# M7050D.net
KiCad netlist of a schematic drawn in EAGLE
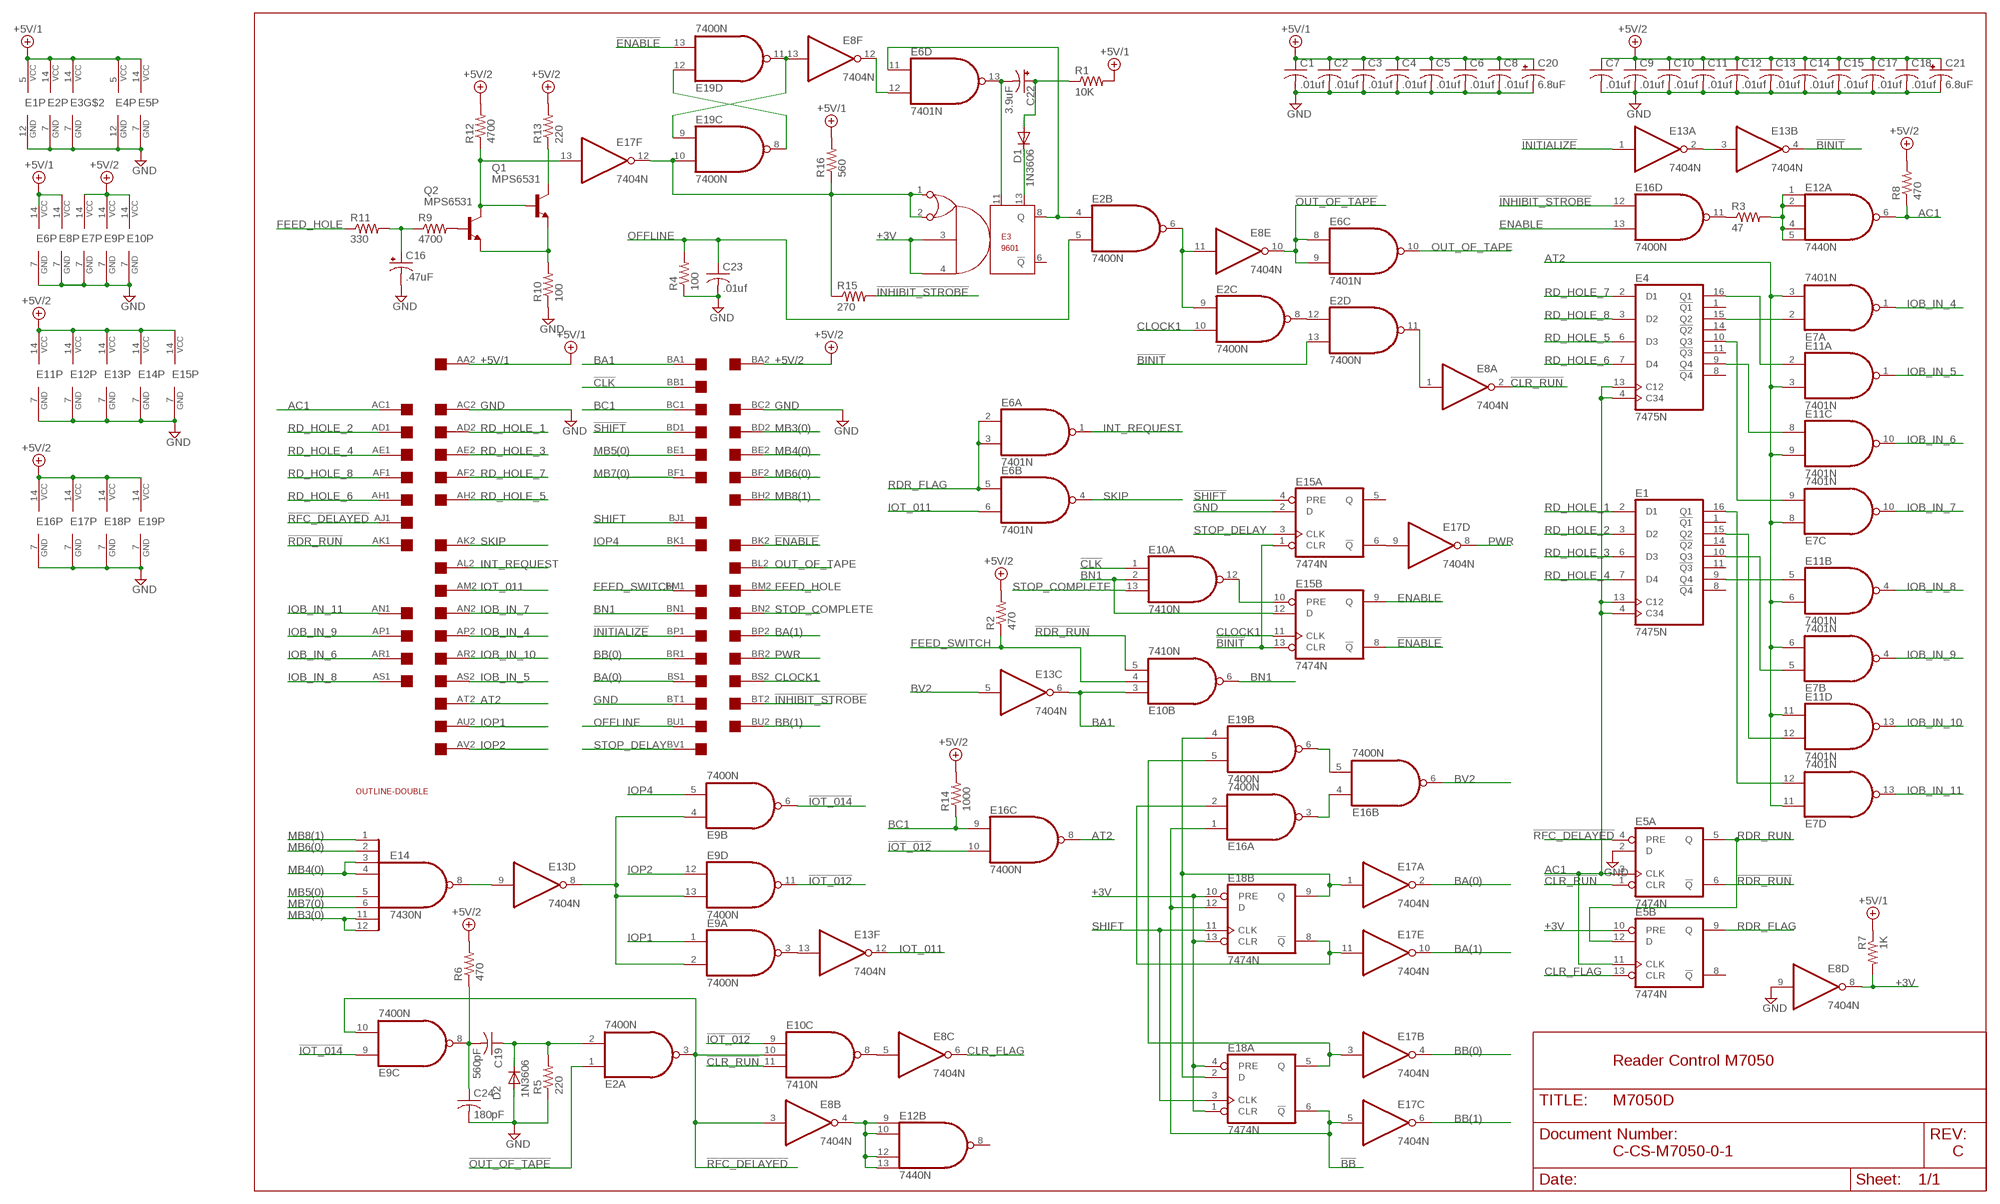
[diagram p0: schematic, sheet 1]

(export (version "E")
  (design (tool "Eeschema 10.0.6"))
  (components
    (comp (ref "C1")
      (value ".01uf")
      (footprint "eagle-import:C075-032X103")
      (libsource (lib "eagle-import") (part "C-US075-032X103"))
    )
    (comp (ref "C2")
      (value ".01uf")
      (footprint "eagle-import:C075-032X103")
      (libsource (lib "eagle-import") (part "C-US075-032X103"))
    )
    (comp (ref "C3")
      (value ".01uf")
      (footprint "eagle-import:C075-032X103")
      (libsource (lib "eagle-import") (part "C-US075-032X103"))
    )
    (comp (ref "C4")
      (value ".01uf")
      (footprint "eagle-import:C075-032X103")
      (libsource (lib "eagle-import") (part "C-US075-032X103"))
    )
    (comp (ref "C5")
      (value ".01uf")
      (footprint "eagle-import:C075-032X103")
      (libsource (lib "eagle-import") (part "C-US075-032X103"))
    )
    (comp (ref "C6")
      (value ".01uf")
      (footprint "eagle-import:C075-032X103")
      (libsource (lib "eagle-import") (part "C-US075-032X103"))
    )
    (comp (ref "C7")
      (value ".01uf")
      (footprint "eagle-import:C075-032X103")
      (libsource (lib "eagle-import") (part "C-US075-032X103"))
    )
    (comp (ref "C8")
      (value ".01uf")
      (footprint "eagle-import:C075-032X103")
      (libsource (lib "eagle-import") (part "C-US075-032X103"))
    )
    (comp (ref "C9")
      (value ".01uf")
      (footprint "eagle-import:C075-032X103")
      (libsource (lib "eagle-import") (part "C-US075-032X103"))
    )
    (comp (ref "C10")
      (value ".01uf")
      (footprint "eagle-import:C075-032X103")
      (libsource (lib "eagle-import") (part "C-US075-032X103"))
    )
    (comp (ref "C11")
      (value ".01uf")
      (footprint "eagle-import:C075-032X103")
      (libsource (lib "eagle-import") (part "C-US075-032X103"))
    )
    (comp (ref "C12")
      (value ".01uf")
      (footprint "eagle-import:C075-032X103")
      (libsource (lib "eagle-import") (part "C-US075-032X103"))
    )
    (comp (ref "C13")
      (value ".01uf")
      (footprint "eagle-import:C075-032X103")
      (libsource (lib "eagle-import") (part "C-US075-032X103"))
    )
    (comp (ref "C14")
      (value ".01uf")
      (footprint "eagle-import:C075-032X103")
      (libsource (lib "eagle-import") (part "C-US075-032X103"))
    )
    (comp (ref "C15")
      (value ".01uf")
      (footprint "eagle-import:C075-032X103")
      (libsource (lib "eagle-import") (part "C-US075-032X103"))
    )
    (comp (ref "C16")
      (value ".47uF")
      (footprint "eagle-import:E15-5")
      (libsource (lib "eagle-import") (part "CPOL-USE15-5AXIAL"))
    )
    (comp (ref "C17")
      (value ".01uf")
      (footprint "eagle-import:C075-032X103")
      (libsource (lib "eagle-import") (part "C-US075-032X103"))
    )
    (comp (ref "C18")
      (value ".01uf")
      (footprint "eagle-import:C075-032X103")
      (libsource (lib "eagle-import") (part "C-US075-032X103"))
    )
    (comp (ref "C19")
      (value "560pF")
      (footprint "eagle-import:C075-032X103")
      (libsource (lib "eagle-import") (part "C-US075-032X103"))
    )
    (comp (ref "C20")
      (value "6.8uF")
      (footprint "eagle-import:E12-8")
      (libsource (lib "eagle-import") (part "CPOL-USE20-8AXIAL"))
    )
    (comp (ref "C21")
      (value "6.8uF")
      (footprint "eagle-import:E12-8")
      (libsource (lib "eagle-import") (part "CPOL-USE20-8AXIAL"))
    )
    (comp (ref "C22")
      (value "3.9uF")
      (footprint "eagle-import:E15-5")
      (libsource (lib "eagle-import") (part "CPOL-USE15-5AXIAL"))
    )
    (comp (ref "C23")
      (value ".01uf")
      (footprint "eagle-import:C075-032X103")
      (libsource (lib "eagle-import") (part "C-US075-032X103"))
    )
    (comp (ref "C24")
      (value "180pF")
      (footprint "eagle-import:C075-032X103")
      (libsource (lib "eagle-import") (part "C-US075-032X103"))
    )
    (comp (ref "D1")
      (value "1N3606")
      (footprint "eagle-import:DO35-10")
      (libsource (lib "eagle-import") (part "1N4148DO35-10"))
    )
    (comp (ref "D2")
      (value "1N3606")
      (footprint "eagle-import:DO35-10")
      (libsource (lib "eagle-import") (part "1N4148DO35-10"))
    )
    (comp (ref "E1")
      (value "7475N")
      (footprint "eagle-import:DIL16")
      (libsource (lib "eagle-import") (part "7475N"))
    )
    (comp (ref "E2")
      (value "7400N")
      (footprint "eagle-import:DIL14")
      (libsource (lib "eagle-import") (part "7400N"))
    )
    (comp (ref "E3")
      (value "9601")
      (footprint "eagle-import:DIL14")
      (libsource (lib "eagle-import") (part "9601"))
    )
    (comp (ref "E4")
      (value "7475N")
      (footprint "eagle-import:DIL16")
      (libsource (lib "eagle-import") (part "7475N"))
    )
    (comp (ref "E5")
      (value "7474N")
      (footprint "eagle-import:DIL14")
      (libsource (lib "eagle-import") (part "7474NS"))
    )
    (comp (ref "E6")
      (value "7401N")
      (footprint "eagle-import:DIL14")
      (libsource (lib "eagle-import") (part "7401NLS"))
    )
    (comp (ref "E7")
      (value "7401N")
      (footprint "eagle-import:DIL14")
      (libsource (lib "eagle-import") (part "7401NLS"))
    )
    (comp (ref "E8")
      (value "7404N")
      (footprint "eagle-import:DIL14")
      (libsource (lib "eagle-import") (part "7404N"))
    )
    (comp (ref "E9")
      (value "7400N")
      (footprint "eagle-import:DIL14")
      (libsource (lib "eagle-import") (part "7400N"))
    )
    (comp (ref "E10")
      (value "7410N")
      (footprint "eagle-import:DIL14")
      (libsource (lib "eagle-import") (part "7410N"))
    )
    (comp (ref "E11")
      (value "7401N")
      (footprint "eagle-import:DIL14")
      (libsource (lib "eagle-import") (part "7401NLS"))
    )
    (comp (ref "E12")
      (value "7440N")
      (footprint "eagle-import:DIL14")
      (libsource (lib "eagle-import") (part "7420NS"))
    )
    (comp (ref "E13")
      (value "7404N")
      (footprint "eagle-import:DIL14")
      (libsource (lib "eagle-import") (part "7404N"))
    )
    (comp (ref "E14")
      (value "7430N")
      (footprint "eagle-import:DIL14")
      (libsource (lib "eagle-import") (part "7430N"))
    )
    (comp (ref "E15")
      (value "7474N")
      (footprint "eagle-import:DIL14")
      (libsource (lib "eagle-import") (part "7474NS"))
    )
    (comp (ref "E16")
      (value "7400N")
      (footprint "eagle-import:DIL14")
      (libsource (lib "eagle-import") (part "7400N"))
    )
    (comp (ref "E17")
      (value "7404N")
      (footprint "eagle-import:DIL14")
      (libsource (lib "eagle-import") (part "7404N"))
    )
    (comp (ref "E18")
      (value "7474N")
      (footprint "eagle-import:DIL14")
      (libsource (lib "eagle-import") (part "7474NS"))
    )
    (comp (ref "E19")
      (value "7400N")
      (footprint "eagle-import:DIL14")
      (libsource (lib "eagle-import") (part "7400N"))
    )
    (comp (ref "Q1")
      (value "MPS6531")
      (footprint "eagle-import:TO5")
      (libsource (lib "eagle-import") (part "2N2102"))
    )
    (comp (ref "Q2")
      (value "MPS6531")
      (footprint "eagle-import:TO5")
      (libsource (lib "eagle-import") (part "2N2102"))
    )
    (comp (ref "R1")
      (value "10K")
      (footprint "eagle-import:0207_10")
      (libsource (lib "eagle-import") (part "R-US_0207/10"))
    )
    (comp (ref "R2")
      (value "470")
      (footprint "eagle-import:0207_10")
      (libsource (lib "eagle-import") (part "R-US_0207/10"))
    )
    (comp (ref "R3")
      (value "47")
      (footprint "eagle-import:0207_10")
      (libsource (lib "eagle-import") (part "R-US_0207/10"))
    )
    (comp (ref "R4")
      (value "100")
      (footprint "eagle-import:0207_10")
      (libsource (lib "eagle-import") (part "R-US_0207/10"))
    )
    (comp (ref "R5")
      (value "220")
      (footprint "eagle-import:0207_10")
      (libsource (lib "eagle-import") (part "R-US_0207/10"))
    )
    (comp (ref "R6")
      (value "470")
      (footprint "eagle-import:0207_10")
      (libsource (lib "eagle-import") (part "R-US_0207/10"))
    )
    (comp (ref "R7")
      (value "1K")
      (footprint "eagle-import:0207_10")
      (libsource (lib "eagle-import") (part "R-US_0207/10"))
    )
    (comp (ref "R8")
      (value "470")
      (footprint "eagle-import:0207_10")
      (libsource (lib "eagle-import") (part "R-US_0207/10"))
    )
    (comp (ref "R9")
      (value "4700")
      (footprint "eagle-import:0207_10")
      (libsource (lib "eagle-import") (part "R-US_0207/10"))
    )
    (comp (ref "R10")
      (value "100")
      (footprint "eagle-import:0207_10")
      (libsource (lib "eagle-import") (part "R-US_0207/10"))
    )
    (comp (ref "R11")
      (value "330")
      (footprint "eagle-import:0207_10")
      (libsource (lib "eagle-import") (part "R-US_0207/10"))
    )
    (comp (ref "R12")
      (value "4700")
      (footprint "eagle-import:0207_10")
      (libsource (lib "eagle-import") (part "R-US_0207/10"))
    )
    (comp (ref "R13")
      (value "220")
      (footprint "eagle-import:0207_10")
      (libsource (lib "eagle-import") (part "R-US_0207/10"))
    )
    (comp (ref "R14")
      (value "1000")
      (footprint "eagle-import:0207_10")
      (libsource (lib "eagle-import") (part "R-US_0207/10"))
    )
    (comp (ref "R15")
      (value "270")
      (footprint "eagle-import:0207_10")
      (libsource (lib "eagle-import") (part "R-US_0207/10"))
    )
    (comp (ref "R16")
      (value "560")
      (footprint "eagle-import:0207_10")
      (libsource (lib "eagle-import") (part "R-US_0207/10"))
    )
    (comp (ref "U$5")
      (value "DOUBLE")
      (footprint "eagle-import:EDGE-CON4")
      (libsource (lib "eagle-import") (part "DOUBLE"))
    )
    (comp (ref "U$6")
      (value "OUTLINE-DOUBLE")
      (footprint "eagle-import:DOUBLE")
      (libsource (lib "eagle-import") (part "OUTLINE-DOUBLE"))
    )
  )
  (nets
    (net (code "1") (name "+5V{slash}1") (class "Default")
      (node (ref "C1") (pin "1") (pinfunction "1_1") (pintype "passive"))
      (node (ref "C2") (pin "1") (pinfunction "1_1") (pintype "passive"))
      (node (ref "C20") (pin "+") (pinfunction "+_+") (pintype "passive"))
      (node (ref "C3") (pin "1") (pinfunction "1_1") (pintype "passive"))
      (node (ref "C4") (pin "1") (pinfunction "1_1") (pintype "passive"))
      (node (ref "C5") (pin "1") (pinfunction "1_1") (pintype "passive"))
      (node (ref "C6") (pin "1") (pinfunction "1_1") (pintype "passive"))
      (node (ref "C8") (pin "1") (pinfunction "1_1") (pintype "passive"))
      (node (ref "E1") (pin "5") (pinfunction "VCC_5") (pintype "power_in"))
      (node (ref "E2") (pin "14") (pinfunction "VCC_14") (pintype "power_in"))
      (node (ref "E3") (pin "14") (pinfunction "VCC_14") (pintype "power_in"))
      (node (ref "E4") (pin "5") (pinfunction "VCC_5") (pintype "power_in"))
      (node (ref "E5") (pin "14") (pinfunction "VCC_14") (pintype "power_in"))
      (node (ref "E6") (pin "14") (pinfunction "VCC_14") (pintype "power_in"))
      (node (ref "E8") (pin "14") (pinfunction "VCC_14") (pintype "power_in"))
      (node (ref "R1") (pin "2") (pinfunction "2_2") (pintype "passive"))
      (node (ref "R16") (pin "2") (pinfunction "2_2") (pintype "passive"))
      (node (ref "R7") (pin "1") (pinfunction "1_1") (pintype "passive"))
      (node (ref "U$5") (pin "AA2") (pinfunction "1_AA2") (pintype "bidirectional"))
    )
    (net (code "2") (name "+5V{slash}2") (class "Default")
      (node (ref "C10") (pin "1") (pinfunction "1_1") (pintype "passive"))
      (node (ref "C11") (pin "1") (pinfunction "1_1") (pintype "passive"))
      (node (ref "C12") (pin "1") (pinfunction "1_1") (pintype "passive"))
      (node (ref "C13") (pin "1") (pinfunction "1_1") (pintype "passive"))
      (node (ref "C14") (pin "1") (pinfunction "1_1") (pintype "passive"))
      (node (ref "C15") (pin "1") (pinfunction "1_1") (pintype "passive"))
      (node (ref "C17") (pin "1") (pinfunction "1_1") (pintype "passive"))
      (node (ref "C18") (pin "1") (pinfunction "1_1") (pintype "passive"))
      (node (ref "C21") (pin "+") (pinfunction "+_+") (pintype "passive"))
      (node (ref "C7") (pin "1") (pinfunction "1_1") (pintype "passive"))
      (node (ref "C9") (pin "1") (pinfunction "1_1") (pintype "passive"))
      (node (ref "E10") (pin "14") (pinfunction "VCC_14") (pintype "power_in"))
      (node (ref "E11") (pin "14") (pinfunction "VCC_14") (pintype "power_in"))
      (node (ref "E12") (pin "14") (pinfunction "VCC_14") (pintype "power_in"))
      (node (ref "E13") (pin "14") (pinfunction "VCC_14") (pintype "power_in"))
      (node (ref "E14") (pin "14") (pinfunction "VCC_14") (pintype "power_in"))
      (node (ref "E15") (pin "14") (pinfunction "VCC_14") (pintype "power_in"))
      (node (ref "E16") (pin "14") (pinfunction "VCC_14") (pintype "power_in"))
      (node (ref "E17") (pin "14") (pinfunction "VCC_14") (pintype "power_in"))
      (node (ref "E18") (pin "14") (pinfunction "VCC_14") (pintype "power_in"))
      (node (ref "E19") (pin "14") (pinfunction "VCC_14") (pintype "power_in"))
      (node (ref "E7") (pin "14") (pinfunction "VCC_14") (pintype "power_in"))
      (node (ref "E9") (pin "14") (pinfunction "VCC_14") (pintype "power_in"))
      (node (ref "R12") (pin "2") (pinfunction "2_2") (pintype "passive"))
      (node (ref "R13") (pin "2") (pinfunction "2_2") (pintype "passive"))
      (node (ref "R14") (pin "2") (pinfunction "2_2") (pintype "passive"))
      (node (ref "R2") (pin "2") (pinfunction "2_2") (pintype "passive"))
      (node (ref "R6") (pin "2") (pinfunction "2_2") (pintype "passive"))
      (node (ref "R8") (pin "2") (pinfunction "2_2") (pintype "passive"))
      (node (ref "U$5") (pin "BA2") (pinfunction "1_BA2") (pintype "bidirectional"))
    )
    (net (code "3") (name "/+3V") (class "Default")
      (node (ref "E18") (pin "1") (pinfunction "CLR_1") (pintype "input"))
      (node (ref "E18") (pin "10") (pinfunction "PRE_10") (pintype "input"))
      (node (ref "E18") (pin "13") (pinfunction "CLR_13") (pintype "input"))
      (node (ref "E18") (pin "4") (pinfunction "PRE_4") (pintype "input"))
      (node (ref "E3") (pin "3") (pinfunction "P$3_3") (pintype "input"))
      (node (ref "E3") (pin "4") (pinfunction "P$4_4") (pintype "input"))
      (node (ref "E5") (pin "10") (pinfunction "PRE_10") (pintype "input"))
      (node (ref "E8") (pin "8") (pinfunction "O_8") (pintype "output"))
      (node (ref "R7") (pin "2") (pinfunction "2_2") (pintype "passive"))
    )
    (net (code "4") (name "/AC1") (class "Default")
      (node (ref "E1") (pin "13") (pinfunction "C12_13") (pintype "input"))
      (node (ref "E1") (pin "4") (pinfunction "C34_4") (pintype "input"))
      (node (ref "E12") (pin "6") (pinfunction "O_6") (pintype "output"))
      (node (ref "E4") (pin "13") (pinfunction "C12_13") (pintype "input"))
      (node (ref "E4") (pin "4") (pinfunction "C34_4") (pintype "input"))
      (node (ref "E5") (pin "11") (pinfunction "CLK_11") (pintype "input"))
      (node (ref "E5") (pin "3") (pinfunction "CLK_3") (pintype "input"))
      (node (ref "R8") (pin "1") (pinfunction "1_1") (pintype "passive"))
      (node (ref "U$5") (pin "AC1") (pinfunction "1_AC1") (pintype "bidirectional"))
    )
    (net (code "5") (name "/AT2") (class "Default")
      (node (ref "E11") (pin "11") (pinfunction "I0_11") (pintype "input"))
      (node (ref "E11") (pin "3") (pinfunction "I1_3") (pintype "input"))
      (node (ref "E11") (pin "6") (pinfunction "I1_6") (pintype "input"))
      (node (ref "E11") (pin "9") (pinfunction "I1_9") (pintype "input"))
      (node (ref "E16") (pin "8") (pinfunction "O_8") (pintype "output"))
      (node (ref "E7") (pin "11") (pinfunction "I0_11") (pintype "input"))
      (node (ref "E7") (pin "3") (pinfunction "I1_3") (pintype "input"))
      (node (ref "E7") (pin "6") (pinfunction "I1_6") (pintype "input"))
      (node (ref "E7") (pin "8") (pinfunction "I0_8") (pintype "input"))
      (node (ref "U$5") (pin "AT2") (pinfunction "1_AT2") (pintype "bidirectional"))
    )
    (net (code "6") (name "/BA(0)") (class "Default")
      (node (ref "E17") (pin "2") (pinfunction "O_2") (pintype "output"))
      (node (ref "U$5") (pin "BS1") (pinfunction "1_BS1") (pintype "bidirectional"))
    )
    (net (code "7") (name "/BA(1)") (class "Default")
      (node (ref "E17") (pin "10") (pinfunction "O_10") (pintype "output"))
      (node (ref "U$5") (pin "BP2") (pinfunction "1_BP2") (pintype "bidirectional"))
    )
    (net (code "8") (name "/BA1") (class "Default")
      (node (ref "E10") (pin "3") (pinfunction "I0_3") (pintype "input"))
      (node (ref "E13") (pin "6") (pinfunction "O_6") (pintype "output"))
      (node (ref "U$5") (pin "BA1") (pinfunction "1_BA1") (pintype "bidirectional"))
    )
    (net (code "9") (name "/BB(0)") (class "Default")
      (node (ref "E17") (pin "4") (pinfunction "O_4") (pintype "output"))
      (node (ref "U$5") (pin "BR1") (pinfunction "1_BR1") (pintype "bidirectional"))
    )
    (net (code "10") (name "/BB(1)") (class "Default")
      (node (ref "E17") (pin "6") (pinfunction "O_6") (pintype "output"))
      (node (ref "U$5") (pin "BU2") (pinfunction "1_BU2") (pintype "bidirectional"))
    )
    (net (code "11") (name "/BC1") (class "Default")
      (node (ref "E16") (pin "9") (pinfunction "I0_9") (pintype "input"))
      (node (ref "R14") (pin "1") (pinfunction "1_1") (pintype "passive"))
      (node (ref "U$5") (pin "BC1") (pinfunction "1_BC1") (pintype "bidirectional"))
    )
    (net (code "12") (name "/BN1") (class "Default")
      (node (ref "E10") (pin "2") (pinfunction "I1_2") (pintype "input"))
      (node (ref "E10") (pin "6") (pinfunction "O_6") (pintype "output"))
      (node (ref "E15") (pin "12") (pinfunction "D_12") (pintype "input"))
      (node (ref "U$5") (pin "BN1") (pinfunction "1_BN1") (pintype "bidirectional"))
    )
    (net (code "13") (name "/BV2") (class "Default")
      (node (ref "E13") (pin "5") (pinfunction "I_5") (pintype "input"))
      (node (ref "E16") (pin "6") (pinfunction "O_6") (pintype "output"))
    )
    (net (code "14") (name "/CLOCK1") (class "Default")
      (node (ref "E15") (pin "11") (pinfunction "CLK_11") (pintype "input"))
      (node (ref "E2") (pin "10") (pinfunction "I1_10") (pintype "input"))
      (node (ref "U$5") (pin "BS2") (pinfunction "1_BS2") (pintype "bidirectional"))
    )
    (net (code "15") (name "/CLR_FLAG") (class "Default")
      (node (ref "E5") (pin "13") (pinfunction "CLR_13") (pintype "input"))
      (node (ref "E8") (pin "6") (pinfunction "O_6") (pintype "output"))
    )
    (net (code "16") (name "/ENABLE") (class "Default")
      (node (ref "E15") (pin "9") (pinfunction "Q_9") (pintype "output"))
      (node (ref "E16") (pin "13") (pinfunction "I1_13") (pintype "input"))
    )
    (net (code "17") (name "/FEED_HOLE") (class "Default")
      (node (ref "R11") (pin "1") (pinfunction "1_1") (pintype "passive"))
      (node (ref "U$5") (pin "BM2") (pinfunction "1_BM2") (pintype "bidirectional"))
    )
    (net (code "18") (name "/FEED_SWITCH") (class "Default")
      (node (ref "E10") (pin "4") (pinfunction "I1_4") (pintype "input"))
      (node (ref "R2") (pin "1") (pinfunction "1_1") (pintype "passive"))
      (node (ref "U$5") (pin "BM1") (pinfunction "1_BM1") (pintype "bidirectional"))
    )
    (net (code "19") (name "/INT_REQUEST") (class "Default")
      (node (ref "E6") (pin "1") (pinfunction "O_1") (pintype "open_collector"))
      (node (ref "U$5") (pin "AL2") (pinfunction "1_AL2") (pintype "bidirectional"))
    )
    (net (code "20") (name "/IOB_IN_4") (class "Default")
      (node (ref "E7") (pin "1") (pinfunction "O_1") (pintype "open_collector"))
      (node (ref "U$5") (pin "AP2") (pinfunction "1_AP2") (pintype "bidirectional"))
    )
    (net (code "21") (name "/IOB_IN_5") (class "Default")
      (node (ref "E11") (pin "1") (pinfunction "O_1") (pintype "open_collector"))
      (node (ref "U$5") (pin "AS2") (pinfunction "1_AS2") (pintype "bidirectional"))
    )
    (net (code "22") (name "/IOB_IN_6") (class "Default")
      (node (ref "E11") (pin "10") (pinfunction "O_10") (pintype "open_collector"))
      (node (ref "U$5") (pin "AR1") (pinfunction "1_AR1") (pintype "bidirectional"))
    )
    (net (code "23") (name "/IOB_IN_7") (class "Default")
      (node (ref "E7") (pin "10") (pinfunction "O_10") (pintype "open_collector"))
      (node (ref "U$5") (pin "AN2") (pinfunction "1_AN2") (pintype "bidirectional"))
    )
    (net (code "24") (name "/IOB_IN_8") (class "Default")
      (node (ref "E11") (pin "4") (pinfunction "O_4") (pintype "open_collector"))
      (node (ref "U$5") (pin "AS1") (pinfunction "1_AS1") (pintype "bidirectional"))
    )
    (net (code "25") (name "/IOB_IN_9") (class "Default")
      (node (ref "E7") (pin "4") (pinfunction "O_4") (pintype "open_collector"))
      (node (ref "U$5") (pin "AP1") (pinfunction "1_AP1") (pintype "bidirectional"))
    )
    (net (code "26") (name "/IOB_IN_10") (class "Default")
      (node (ref "E11") (pin "13") (pinfunction "O_13") (pintype "open_collector"))
      (node (ref "U$5") (pin "AR2") (pinfunction "1_AR2") (pintype "bidirectional"))
    )
    (net (code "27") (name "/IOB_IN_11") (class "Default")
      (node (ref "E7") (pin "13") (pinfunction "O_13") (pintype "open_collector"))
      (node (ref "U$5") (pin "AN1") (pinfunction "1_AN1") (pintype "bidirectional"))
    )
    (net (code "28") (name "/IOP1") (class "Default")
      (node (ref "E9") (pin "1") (pinfunction "I0_1") (pintype "input"))
      (node (ref "U$5") (pin "AU2") (pinfunction "1_AU2") (pintype "bidirectional"))
    )
    (net (code "29") (name "/IOP2") (class "Default")
      (node (ref "E9") (pin "12") (pinfunction "I0_12") (pintype "input"))
      (node (ref "U$5") (pin "AV2") (pinfunction "1_AV2") (pintype "bidirectional"))
    )
    (net (code "30") (name "/IOP4") (class "Default")
      (node (ref "E9") (pin "5") (pinfunction "I1_5") (pintype "input"))
      (node (ref "U$5") (pin "BK1") (pinfunction "1_BK1") (pintype "bidirectional"))
    )
    (net (code "31") (name "/IOT_011") (class "Default")
      (node (ref "E13") (pin "12") (pinfunction "O_12") (pintype "output"))
      (node (ref "E6") (pin "6") (pinfunction "I1_6") (pintype "input"))
      (node (ref "U$5") (pin "AM2") (pinfunction "1_AM2") (pintype "bidirectional"))
    )
    (net (code "32") (name "/MB3(0)") (class "Default")
      (node (ref "E14") (pin "11") (pinfunction "I6_11") (pintype "input"))
      (node (ref "E14") (pin "12") (pinfunction "I7_12") (pintype "input"))
      (node (ref "U$5") (pin "BD2") (pinfunction "1_BD2") (pintype "bidirectional"))
    )
    (net (code "33") (name "/MB4(0)") (class "Default")
      (node (ref "E14") (pin "3") (pinfunction "I2_3") (pintype "input"))
      (node (ref "E14") (pin "4") (pinfunction "I3_4") (pintype "input"))
      (node (ref "U$5") (pin "BE2") (pinfunction "1_BE2") (pintype "bidirectional"))
    )
    (net (code "34") (name "/MB5(0)") (class "Default")
      (node (ref "E14") (pin "5") (pinfunction "I4_5") (pintype "input"))
      (node (ref "U$5") (pin "BE1") (pinfunction "1_BE1") (pintype "bidirectional"))
    )
    (net (code "35") (name "/MB6(0)") (class "Default")
      (node (ref "E14") (pin "2") (pinfunction "I1_2") (pintype "input"))
      (node (ref "U$5") (pin "BF2") (pinfunction "1_BF2") (pintype "bidirectional"))
    )
    (net (code "36") (name "/MB7(0)") (class "Default")
      (node (ref "E14") (pin "6") (pinfunction "I5_6") (pintype "input"))
      (node (ref "U$5") (pin "BF1") (pinfunction "1_BF1") (pintype "bidirectional"))
    )
    (net (code "37") (name "/MB8(1)") (class "Default")
      (node (ref "E14") (pin "1") (pinfunction "I0_1") (pintype "input"))
      (node (ref "U$5") (pin "BH2") (pinfunction "1_BH2") (pintype "bidirectional"))
    )
    (net (code "38") (name "/OFFLINE") (class "Default")
      (node (ref "C23") (pin "1") (pinfunction "1_1") (pintype "passive"))
      (node (ref "E2") (pin "5") (pinfunction "I1_5") (pintype "input"))
      (node (ref "R4") (pin "2") (pinfunction "2_2") (pintype "passive"))
      (node (ref "U$5") (pin "BU1") (pinfunction "1_BU1") (pintype "bidirectional"))
    )
    (net (code "39") (name "/OUT_OF_TAPE") (class "Default")
      (node (ref "E6") (pin "10") (pinfunction "O_10") (pintype "open_collector"))
      (node (ref "U$5") (pin "BL2") (pinfunction "1_BL2") (pintype "bidirectional"))
    )
    (net (code "40") (name "/PWR") (class "Default")
      (node (ref "E17") (pin "8") (pinfunction "O_8") (pintype "output"))
      (node (ref "U$5") (pin "BR2") (pinfunction "1_BR2") (pintype "bidirectional"))
    )
    (net (code "41") (name "/RDR_FLAG") (class "Default")
      (node (ref "E5") (pin "9") (pinfunction "Q_9") (pintype "output"))
      (node (ref "E6") (pin "2") (pinfunction "I0_2") (pintype "input"))
      (node (ref "E6") (pin "3") (pinfunction "I1_3") (pintype "input"))
      (node (ref "E6") (pin "5") (pinfunction "I0_5") (pintype "input"))
    )
    (net (code "42") (name "/RDR_RUN") (class "Default")
      (node (ref "E5") (pin "12") (pinfunction "D_12") (pintype "input"))
      (node (ref "E5") (pin "5") (pinfunction "Q_5") (pintype "output"))
    )
    (net (code "43") (name "/RD_HOLE_1") (class "Default")
      (node (ref "E1") (pin "2") (pinfunction "D1_2") (pintype "input"))
      (node (ref "U$5") (pin "AD2") (pinfunction "1_AD2") (pintype "bidirectional"))
    )
    (net (code "44") (name "/RD_HOLE_2") (class "Default")
      (node (ref "E1") (pin "3") (pinfunction "D2_3") (pintype "input"))
      (node (ref "U$5") (pin "AD1") (pinfunction "1_AD1") (pintype "bidirectional"))
    )
    (net (code "45") (name "/RD_HOLE_3") (class "Default")
      (node (ref "E1") (pin "6") (pinfunction "D3_6") (pintype "input"))
      (node (ref "U$5") (pin "AE2") (pinfunction "1_AE2") (pintype "bidirectional"))
    )
    (net (code "46") (name "/RD_HOLE_4") (class "Default")
      (node (ref "E1") (pin "7") (pinfunction "D4_7") (pintype "input"))
      (node (ref "U$5") (pin "AE1") (pinfunction "1_AE1") (pintype "bidirectional"))
    )
    (net (code "47") (name "/RD_HOLE_5") (class "Default")
      (node (ref "E4") (pin "6") (pinfunction "D3_6") (pintype "input"))
      (node (ref "U$5") (pin "AH2") (pinfunction "1_AH2") (pintype "bidirectional"))
    )
    (net (code "48") (name "/RD_HOLE_6") (class "Default")
      (node (ref "E4") (pin "7") (pinfunction "D4_7") (pintype "input"))
      (node (ref "U$5") (pin "AH1") (pinfunction "1_AH1") (pintype "bidirectional"))
    )
    (net (code "49") (name "/RD_HOLE_7") (class "Default")
      (node (ref "E4") (pin "2") (pinfunction "D1_2") (pintype "input"))
      (node (ref "U$5") (pin "AF2") (pinfunction "1_AF2") (pintype "bidirectional"))
    )
    (net (code "50") (name "/RD_HOLE_8") (class "Default")
      (node (ref "E4") (pin "3") (pinfunction "D2_3") (pintype "input"))
      (node (ref "U$5") (pin "AF1") (pinfunction "1_AF1") (pintype "bidirectional"))
    )
    (net (code "51") (name "/SHIFT") (class "Default")
      (node (ref "E18") (pin "11") (pinfunction "CLK_11") (pintype "input"))
      (node (ref "E18") (pin "3") (pinfunction "CLK_3") (pintype "input"))
      (node (ref "U$5") (pin "BJ1") (pinfunction "1_BJ1") (pintype "bidirectional"))
    )
    (net (code "52") (name "/SKIP") (class "Default")
      (node (ref "E6") (pin "4") (pinfunction "O_4") (pintype "open_collector"))
      (node (ref "U$5") (pin "AK2") (pinfunction "1_AK2") (pintype "bidirectional"))
    )
    (net (code "53") (name "/STOP_COMPLETE") (class "Default")
      (node (ref "E10") (pin "13") (pinfunction "I2_13") (pintype "input"))
      (node (ref "U$5") (pin "BN2") (pinfunction "1_BN2") (pintype "bidirectional"))
    )
    (net (code "54") (name "/STOP_DELAY") (class "Default")
      (node (ref "E15") (pin "3") (pinfunction "CLK_3") (pintype "input"))
      (node (ref "U$5") (pin "BV1") (pinfunction "1_BV1") (pintype "bidirectional"))
    )
    (net (code "55") (name "/~{BB}") (class "Default")
      (node (ref "E16") (pin "1") (pinfunction "I0_1") (pintype "input"))
      (node (ref "E17") (pin "5") (pinfunction "I_5") (pintype "input"))
      (node (ref "E18") (pin "12") (pinfunction "D_12") (pintype "input"))
      (node (ref "E18") (pin "6") (pinfunction "~{Q}_6") (pintype "output"))
    )
    (net (code "56") (name "/~{BINIT}") (class "Default")
      (node (ref "E13") (pin "4") (pinfunction "O_4") (pintype "output"))
      (node (ref "E15") (pin "1") (pinfunction "CLR_1") (pintype "input"))
      (node (ref "E15") (pin "13") (pinfunction "CLR_13") (pintype "input"))
      (node (ref "E2") (pin "13") (pinfunction "I1_13") (pintype "input"))
    )
    (net (code "57") (name "/~{CLK}") (class "Default")
      (node (ref "E10") (pin "1") (pinfunction "I0_1") (pintype "input"))
      (node (ref "U$5") (pin "BB1") (pinfunction "1_BB1") (pintype "bidirectional"))
    )
    (net (code "58") (name "/~{CLR_RUN}") (class "Default")
      (node (ref "E10") (pin "11") (pinfunction "I2_11") (pintype "input"))
      (node (ref "E5") (pin "1") (pinfunction "CLR_1") (pintype "input"))
      (node (ref "E8") (pin "2") (pinfunction "O_2") (pintype "output"))
    )
    (net (code "59") (name "/~{ENABLE}") (class "Default")
      (node (ref "E15") (pin "8") (pinfunction "~{Q}_8") (pintype "output"))
      (node (ref "E19") (pin "13") (pinfunction "I1_13") (pintype "input"))
      (node (ref "U$5") (pin "BK2") (pinfunction "1_BK2") (pintype "bidirectional"))
    )
    (net (code "60") (name "/~{INHIBIT_STROBE}") (class "Default")
      (node (ref "E16") (pin "12") (pinfunction "I0_12") (pintype "input"))
      (node (ref "R15") (pin "2") (pinfunction "2_2") (pintype "passive"))
      (node (ref "U$5") (pin "BT2") (pinfunction "1_BT2") (pintype "bidirectional"))
    )
    (net (code "61") (name "/~{INITIALIZE}") (class "Default")
      (node (ref "E13") (pin "1") (pinfunction "I_1") (pintype "input"))
      (node (ref "U$5") (pin "BP1") (pinfunction "1_BP1") (pintype "bidirectional"))
    )
    (net (code "62") (name "/~{IOT_012}") (class "Default")
      (node (ref "E10") (pin "9") (pinfunction "I0_9") (pintype "input"))
      (node (ref "E16") (pin "10") (pinfunction "I1_10") (pintype "input"))
      (node (ref "E9") (pin "11") (pinfunction "O_11") (pintype "output"))
    )
    (net (code "63") (name "/~{IOT_014}") (class "Default")
      (node (ref "E9") (pin "6") (pinfunction "O_6") (pintype "output"))
      (node (ref "E9") (pin "9") (pinfunction "I0_9") (pintype "input"))
    )
    (net (code "64") (name "/~{OUT_OF_TAPE}") (class "Default")
      (node (ref "E2") (pin "1") (pinfunction "I0_1") (pintype "input"))
      (node (ref "E6") (pin "8") (pinfunction "I0_8") (pintype "input"))
      (node (ref "E6") (pin "9") (pinfunction "I1_9") (pintype "input"))
      (node (ref "E8") (pin "10") (pinfunction "O_10") (pintype "output"))
    )
    (net (code "65") (name "/~{RDR_RUN}") (class "Default")
      (node (ref "E10") (pin "5") (pinfunction "I2_5") (pintype "input"))
      (node (ref "E5") (pin "6") (pinfunction "~{Q}_6") (pintype "output"))
      (node (ref "U$5") (pin "AK1") (pinfunction "1_AK1") (pintype "bidirectional"))
    )
    (net (code "66") (name "/~{RFC_DELAYED}") (class "Default")
      (node (ref "E10") (pin "10") (pinfunction "I1_10") (pintype "input"))
      (node (ref "E2") (pin "3") (pinfunction "O_3") (pintype "output"))
      (node (ref "E5") (pin "4") (pinfunction "PRE_4") (pintype "input"))
      (node (ref "E8") (pin "3") (pinfunction "I_3") (pintype "input"))
      (node (ref "E9") (pin "10") (pinfunction "I1_10") (pintype "input"))
      (node (ref "U$5") (pin "AJ1") (pinfunction "1_AJ1") (pintype "bidirectional"))
    )
    (net (code "67") (name "/~{SHIFT}") (class "Default")
      (node (ref "E15") (pin "4") (pinfunction "PRE_4") (pintype "input"))
      (node (ref "U$5") (pin "BD1") (pinfunction "1_BD1") (pintype "bidirectional"))
    )
    (net (code "68") (name "GND") (class "Default")
      (node (ref "C1") (pin "2") (pinfunction "2_2") (pintype "passive"))
      (node (ref "C10") (pin "2") (pinfunction "2_2") (pintype "passive"))
      (node (ref "C11") (pin "2") (pinfunction "2_2") (pintype "passive"))
      (node (ref "C12") (pin "2") (pinfunction "2_2") (pintype "passive"))
      (node (ref "C13") (pin "2") (pinfunction "2_2") (pintype "passive"))
      (node (ref "C14") (pin "2") (pinfunction "2_2") (pintype "passive"))
      (node (ref "C15") (pin "2") (pinfunction "2_2") (pintype "passive"))
      (node (ref "C16") (pin "-") (pinfunction "-_-") (pintype "passive"))
      (node (ref "C17") (pin "2") (pinfunction "2_2") (pintype "passive"))
      (node (ref "C18") (pin "2") (pinfunction "2_2") (pintype "passive"))
      (node (ref "C2") (pin "2") (pinfunction "2_2") (pintype "passive"))
      (node (ref "C20") (pin "-") (pinfunction "-_-") (pintype "passive"))
      (node (ref "C21") (pin "-") (pinfunction "-_-") (pintype "passive"))
      (node (ref "C23") (pin "2") (pinfunction "2_2") (pintype "passive"))
      (node (ref "C24") (pin "2") (pinfunction "2_2") (pintype "passive"))
      (node (ref "C3") (pin "2") (pinfunction "2_2") (pintype "passive"))
      (node (ref "C4") (pin "2") (pinfunction "2_2") (pintype "passive"))
      (node (ref "C5") (pin "2") (pinfunction "2_2") (pintype "passive"))
      (node (ref "C6") (pin "2") (pinfunction "2_2") (pintype "passive"))
      (node (ref "C7") (pin "2") (pinfunction "2_2") (pintype "passive"))
      (node (ref "C8") (pin "2") (pinfunction "2_2") (pintype "passive"))
      (node (ref "C9") (pin "2") (pinfunction "2_2") (pintype "passive"))
      (node (ref "D2") (pin "A") (pinfunction "A_A") (pintype "passive"))
      (node (ref "E1") (pin "12") (pinfunction "GND_12") (pintype "power_in"))
      (node (ref "E10") (pin "7") (pinfunction "GND_7") (pintype "power_in"))
      (node (ref "E11") (pin "7") (pinfunction "GND_7") (pintype "power_in"))
      (node (ref "E12") (pin "7") (pinfunction "GND_7") (pintype "power_in"))
      (node (ref "E13") (pin "7") (pinfunction "GND_7") (pintype "power_in"))
      (node (ref "E14") (pin "7") (pinfunction "GND_7") (pintype "power_in"))
      (node (ref "E15") (pin "2") (pinfunction "D_2") (pintype "input"))
      (node (ref "E15") (pin "7") (pinfunction "GND_7") (pintype "power_in"))
      (node (ref "E16") (pin "7") (pinfunction "GND_7") (pintype "power_in"))
      (node (ref "E17") (pin "7") (pinfunction "GND_7") (pintype "power_in"))
      (node (ref "E18") (pin "7") (pinfunction "GND_7") (pintype "power_in"))
      (node (ref "E19") (pin "7") (pinfunction "GND_7") (pintype "power_in"))
      (node (ref "E2") (pin "7") (pinfunction "GND_7") (pintype "power_in"))
      (node (ref "E3") (pin "7") (pinfunction "GND_7") (pintype "power_in"))
      (node (ref "E4") (pin "12") (pinfunction "GND_12") (pintype "power_in"))
      (node (ref "E5") (pin "2") (pinfunction "D_2") (pintype "input"))
      (node (ref "E5") (pin "7") (pinfunction "GND_7") (pintype "power_in"))
      (node (ref "E6") (pin "7") (pinfunction "GND_7") (pintype "power_in"))
      (node (ref "E7") (pin "7") (pinfunction "GND_7") (pintype "power_in"))
      (node (ref "E8") (pin "7") (pinfunction "GND_7") (pintype "power_in"))
      (node (ref "E8") (pin "9") (pinfunction "I_9") (pintype "input"))
      (node (ref "E9") (pin "7") (pinfunction "GND_7") (pintype "power_in"))
      (node (ref "R10") (pin "1") (pinfunction "1_1") (pintype "passive"))
      (node (ref "R4") (pin "1") (pinfunction "1_1") (pintype "passive"))
      (node (ref "R5") (pin "1") (pinfunction "1_1") (pintype "passive"))
      (node (ref "U$5") (pin "AC2") (pinfunction "1_AC2") (pintype "bidirectional"))
      (node (ref "U$5") (pin "BC2") (pinfunction "1_BC2") (pintype "bidirectional"))
      (node (ref "U$5") (pin "BT1") (pinfunction "1_BT1") (pintype "bidirectional"))
    )
    (net (code "69") (name "Net-(C16-Pad+)") (class "Default")
      (node (ref "C16") (pin "+") (pinfunction "+_+") (pintype "passive"))
      (node (ref "R11") (pin "2") (pinfunction "2_2") (pintype "passive"))
      (node (ref "R9") (pin "1") (pinfunction "1_1") (pintype "passive"))
    )
    (net (code "70") (name "Net-(C22-Pad+)") (class "Default")
      (node (ref "C22") (pin "+") (pinfunction "+_+") (pintype "passive"))
      (node (ref "D1") (pin "A") (pinfunction "A_A") (pintype "passive"))
      (node (ref "R1") (pin "1") (pinfunction "1_1") (pintype "passive"))
    )
    (net (code "71") (name "Net-(E1A-Q1)") (class "Default")
      (node (ref "E1") (pin "16") (pinfunction "Q1_16") (pintype "output"))
      (node (ref "E7") (pin "12") (pinfunction "I1_12") (pintype "input"))
    )
    (net (code "72") (name "Net-(E1A-Q3)") (class "Default")
      (node (ref "E1") (pin "10") (pinfunction "Q3_10") (pintype "output"))
      (node (ref "E7") (pin "5") (pinfunction "I0_5") (pintype "input"))
    )
    (net (code "73") (name "Net-(E2A-I1)") (class "Default")
      (node (ref "C19") (pin "1") (pinfunction "1_1") (pintype "passive"))
      (node (ref "D2") (pin "C") (pinfunction "C_C") (pintype "passive"))
      (node (ref "E2") (pin "2") (pinfunction "I1_2") (pintype "input"))
      (node (ref "R5") (pin "2") (pinfunction "2_2") (pintype "passive"))
    )
    (net (code "74") (name "Net-(E2B-I0)") (class "Default")
      (node (ref "E2") (pin "4") (pinfunction "I0_4") (pintype "input"))
      (node (ref "E3") (pin "8") (pinfunction "Q_8") (pintype "output"))
      (node (ref "E6") (pin "11") (pinfunction "I0_11") (pintype "input"))
    )
    (net (code "75") (name "Net-(E2B-O)") (class "Default")
      (node (ref "E2") (pin "6") (pinfunction "O_6") (pintype "output"))
      (node (ref "E2") (pin "9") (pinfunction "I0_9") (pintype "input"))
      (node (ref "E8") (pin "11") (pinfunction "I_11") (pintype "input"))
    )
    (net (code "76") (name "Net-(E2C-O)") (class "Default")
      (node (ref "E2") (pin "12") (pinfunction "I0_12") (pintype "input"))
      (node (ref "E2") (pin "8") (pinfunction "O_8") (pintype "output"))
    )
    (net (code "77") (name "Net-(E2D-O)") (class "Default")
      (node (ref "E2") (pin "11") (pinfunction "O_11") (pintype "output"))
      (node (ref "E8") (pin "1") (pinfunction "I_1") (pintype "input"))
    )
    (net (code "78") (name "Net-(E3A-P$5)") (class "Default")
      (node (ref "C22") (pin "-") (pinfunction "-_-") (pintype "passive"))
      (node (ref "E3") (pin "11") (pinfunction "P$5_11") (pintype "bidirectional"))
      (node (ref "E6") (pin "13") (pinfunction "O_13") (pintype "open_collector"))
    )
    (net (code "79") (name "Net-(E3A-P$6)") (class "Default")
      (node (ref "D1") (pin "C") (pinfunction "C_C") (pintype "passive"))
      (node (ref "E3") (pin "13") (pinfunction "P$6_13") (pintype "bidirectional"))
    )
    (net (code "80") (name "Net-(E4A-Q2)") (class "Default")
      (node (ref "E4") (pin "15") (pinfunction "Q2_15") (pintype "output"))
      (node (ref "E7") (pin "2") (pinfunction "I0_2") (pintype "input"))
    )
    (net (code "81") (name "Net-(E4A-Q3)") (class "Default")
      (node (ref "E4") (pin "10") (pinfunction "Q3_10") (pintype "output"))
      (node (ref "E7") (pin "9") (pinfunction "I1_9") (pintype "input"))
    )
    (net (code "82") (name "Net-(E6D-I1)") (class "Default")
      (node (ref "E6") (pin "12") (pinfunction "I1_12") (pintype "input"))
      (node (ref "E8") (pin "12") (pinfunction "O_12") (pintype "output"))
    )
    (net (code "83") (name "Net-(E9C-O)") (class "Default")
      (node (ref "C19") (pin "2") (pinfunction "2_2") (pintype "passive"))
      (node (ref "C24") (pin "1") (pinfunction "1_1") (pintype "passive"))
      (node (ref "E9") (pin "8") (pinfunction "O_8") (pintype "output"))
      (node (ref "R6") (pin "1") (pinfunction "1_1") (pintype "passive"))
    )
    (net (code "84") (name "Net-(E10A-O)") (class "Default")
      (node (ref "E10") (pin "12") (pinfunction "O_12") (pintype "output"))
      (node (ref "E15") (pin "10") (pinfunction "PRE_10") (pintype "input"))
    )
    (net (code "85") (name "Net-(E10C-O)") (class "Default")
      (node (ref "E10") (pin "8") (pinfunction "O_8") (pintype "output"))
      (node (ref "E8") (pin "5") (pinfunction "I_5") (pintype "input"))
    )
    (net (code "86") (name "Net-(E11A-I0)") (class "Default")
      (node (ref "E11") (pin "2") (pinfunction "I0_2") (pintype "input"))
      (node (ref "E4") (pin "16") (pinfunction "Q1_16") (pintype "output"))
    )
    (net (code "87") (name "Net-(E11B-I0)") (class "Default")
      (node (ref "E1") (pin "9") (pinfunction "Q4_9") (pintype "output"))
      (node (ref "E11") (pin "5") (pinfunction "I0_5") (pintype "input"))
    )
    (net (code "88") (name "Net-(E11C-I0)") (class "Default")
      (node (ref "E11") (pin "8") (pinfunction "I0_8") (pintype "input"))
      (node (ref "E4") (pin "9") (pinfunction "Q4_9") (pintype "output"))
    )
    (net (code "89") (name "Net-(E11D-I1)") (class "Default")
      (node (ref "E1") (pin "15") (pinfunction "Q2_15") (pintype "output"))
      (node (ref "E11") (pin "12") (pinfunction "I1_12") (pintype "input"))
    )
    (net (code "90") (name "Net-(E12A-I0)") (class "Default")
      (node (ref "E12") (pin "1") (pinfunction "I0_1") (pintype "input"))
      (node (ref "E12") (pin "2") (pinfunction "I1_2") (pintype "input"))
      (node (ref "E12") (pin "4") (pinfunction "I2_4") (pintype "input"))
      (node (ref "E12") (pin "5") (pinfunction "I3_5") (pintype "input"))
      (node (ref "R3") (pin "2") (pinfunction "2_2") (pintype "passive"))
    )
    (net (code "91") (name "Net-(E12B-I0)") (class "Default")
      (node (ref "E12") (pin "10") (pinfunction "I1_10") (pintype "input"))
      (node (ref "E12") (pin "12") (pinfunction "I2_12") (pintype "input"))
      (node (ref "E12") (pin "13") (pinfunction "I3_13") (pintype "input"))
      (node (ref "E12") (pin "9") (pinfunction "I0_9") (pintype "input"))
      (node (ref "E8") (pin "4") (pinfunction "O_4") (pintype "output"))
    )
    (net (code "92") (name "Net-(E13A-O)") (class "Default")
      (node (ref "E13") (pin "2") (pinfunction "O_2") (pintype "output"))
      (node (ref "E13") (pin "3") (pinfunction "I_3") (pintype "input"))
    )
    (net (code "93") (name "Net-(E13D-I)") (class "Default")
      (node (ref "E13") (pin "9") (pinfunction "I_9") (pintype "input"))
      (node (ref "E14") (pin "8") (pinfunction "O_8") (pintype "output"))
    )
    (net (code "94") (name "Net-(E13D-O)") (class "Default")
      (node (ref "E13") (pin "8") (pinfunction "O_8") (pintype "output"))
      (node (ref "E9") (pin "13") (pinfunction "I1_13") (pintype "input"))
      (node (ref "E9") (pin "2") (pinfunction "I1_2") (pintype "input"))
      (node (ref "E9") (pin "4") (pinfunction "I0_4") (pintype "input"))
    )
    (net (code "95") (name "Net-(E13F-I)") (class "Default")
      (node (ref "E13") (pin "13") (pinfunction "I_13") (pintype "input"))
      (node (ref "E9") (pin "3") (pinfunction "O_3") (pintype "output"))
    )
    (net (code "96") (name "Net-(E15A-~{Q})") (class "Default")
      (node (ref "E15") (pin "6") (pinfunction "~{Q}_6") (pintype "output"))
      (node (ref "E17") (pin "9") (pinfunction "I_9") (pintype "input"))
    )
    (net (code "97") (name "Net-(E16A-I1)") (class "Default")
      (node (ref "E16") (pin "2") (pinfunction "I1_2") (pintype "input"))
      (node (ref "E17") (pin "11") (pinfunction "I_11") (pintype "input"))
      (node (ref "E18") (pin "8") (pinfunction "~{Q}_8") (pintype "output"))
    )
    (net (code "98") (name "Net-(E16A-O)") (class "Default")
      (node (ref "E16") (pin "3") (pinfunction "O_3") (pintype "output"))
      (node (ref "E16") (pin "4") (pinfunction "I0_4") (pintype "input"))
    )
    (net (code "99") (name "Net-(E16B-I1)") (class "Default")
      (node (ref "E16") (pin "5") (pinfunction "I1_5") (pintype "input"))
      (node (ref "E19") (pin "6") (pinfunction "O_6") (pintype "output"))
    )
    (net (code "100") (name "Net-(E16D-O)") (class "Default")
      (node (ref "E16") (pin "11") (pinfunction "O_11") (pintype "output"))
      (node (ref "R3") (pin "1") (pinfunction "1_1") (pintype "passive"))
    )
    (net (code "101") (name "Net-(E17A-I)") (class "Default")
      (node (ref "E17") (pin "1") (pinfunction "I_1") (pintype "input"))
      (node (ref "E18") (pin "2") (pinfunction "D_2") (pintype "input"))
      (node (ref "E18") (pin "9") (pinfunction "Q_9") (pintype "output"))
      (node (ref "E19") (pin "4") (pinfunction "I0_4") (pintype "input"))
    )
    (net (code "102") (name "Net-(E17B-I)") (class "Default")
      (node (ref "E17") (pin "3") (pinfunction "I_3") (pintype "input"))
      (node (ref "E18") (pin "5") (pinfunction "Q_5") (pintype "output"))
      (node (ref "E19") (pin "5") (pinfunction "I1_5") (pintype "input"))
    )
    (net (code "103") (name "Net-(E17F-I)") (class "Default")
      (node (ref "E17") (pin "13") (pinfunction "I_13") (pintype "input"))
      (node (ref "Q1") (pin "2") (pinfunction "B_2") (pintype "passive"))
      (node (ref "Q2") (pin "3") (pinfunction "C_3") (pintype "passive"))
      (node (ref "R12") (pin "1") (pinfunction "1_1") (pintype "passive"))
    )
    (net (code "104") (name "Net-(E17F-O)") (class "Default")
      (node (ref "E17") (pin "12") (pinfunction "O_12") (pintype "output"))
      (node (ref "E19") (pin "10") (pinfunction "I1_10") (pintype "input"))
      (node (ref "E3") (pin "1") (pinfunction "P$1_1") (pintype "input"))
      (node (ref "E3") (pin "2") (pinfunction "P$2_2") (pintype "input"))
      (node (ref "R15") (pin "1") (pinfunction "1_1") (pintype "passive"))
      (node (ref "R16") (pin "1") (pinfunction "1_1") (pintype "passive"))
    )
    (net (code "105") (name "Net-(E19C-I0)") (class "Default")
      (node (ref "E19") (pin "11") (pinfunction "O_11") (pintype "output"))
      (node (ref "E19") (pin "9") (pinfunction "I0_9") (pintype "input"))
      (node (ref "E8") (pin "13") (pinfunction "I_13") (pintype "input"))
    )
    (net (code "106") (name "Net-(E19C-O)") (class "Default")
      (node (ref "E19") (pin "12") (pinfunction "I0_12") (pintype "input"))
      (node (ref "E19") (pin "8") (pinfunction "O_8") (pintype "output"))
    )
    (net (code "107") (name "Net-(Q1-C)") (class "Default")
      (node (ref "Q1") (pin "3") (pinfunction "C_3") (pintype "passive"))
      (node (ref "R13") (pin "1") (pinfunction "1_1") (pintype "passive"))
    )
    (net (code "108") (name "Net-(Q1-E)") (class "Default")
      (node (ref "Q1") (pin "1") (pinfunction "E_1") (pintype "passive"))
      (node (ref "Q2") (pin "1") (pinfunction "E_1") (pintype "passive"))
      (node (ref "R10") (pin "2") (pinfunction "2_2") (pintype "passive"))
    )
    (net (code "109") (name "Net-(Q2-B)") (class "Default")
      (node (ref "Q2") (pin "2") (pinfunction "B_2") (pintype "passive"))
      (node (ref "R9") (pin "2") (pinfunction "2_2") (pintype "passive"))
    )
    (net (code "110") (name "unconnected-(E1A-~{Q1}-Pad1)") (class "Default")
      (node (ref "E1") (pin "1") (pinfunction "~{Q1}_1") (pintype "output"))
    )
    (net (code "111") (name "unconnected-(E1A-~{Q2}-Pad14)") (class "Default")
      (node (ref "E1") (pin "14") (pinfunction "~{Q2}_14") (pintype "output"))
    )
    (net (code "112") (name "unconnected-(E1A-~{Q3}-Pad11)") (class "Default")
      (node (ref "E1") (pin "11") (pinfunction "~{Q3}_11") (pintype "output"))
    )
    (net (code "113") (name "unconnected-(E1A-~{Q4}-Pad8)") (class "Default")
      (node (ref "E1") (pin "8") (pinfunction "~{Q4}_8") (pintype "output"))
    )
    (net (code "114") (name "unconnected-(E3A-~{Q}-Pad6)") (class "Default")
      (node (ref "E3") (pin "6") (pinfunction "~{Q}_6") (pintype "output"))
    )
    (net (code "115") (name "unconnected-(E4A-~{Q1}-Pad1)") (class "Default")
      (node (ref "E4") (pin "1") (pinfunction "~{Q1}_1") (pintype "output"))
    )
    (net (code "116") (name "unconnected-(E4A-~{Q2}-Pad14)") (class "Default")
      (node (ref "E4") (pin "14") (pinfunction "~{Q2}_14") (pintype "output"))
    )
    (net (code "117") (name "unconnected-(E4A-~{Q3}-Pad11)") (class "Default")
      (node (ref "E4") (pin "11") (pinfunction "~{Q3}_11") (pintype "output"))
    )
    (net (code "118") (name "unconnected-(E4A-~{Q4}-Pad8)") (class "Default")
      (node (ref "E4") (pin "8") (pinfunction "~{Q4}_8") (pintype "output"))
    )
    (net (code "119") (name "unconnected-(E5B-~{Q}-Pad8)") (class "Default")
      (node (ref "E5") (pin "8") (pinfunction "~{Q}_8") (pintype "output"))
    )
    (net (code "120") (name "unconnected-(E12B-O-Pad8)") (class "Default")
      (node (ref "E12") (pin "8") (pinfunction "O_8") (pintype "output"))
    )
    (net (code "121") (name "unconnected-(E15A-Q-Pad5)") (class "Default")
      (node (ref "E15") (pin "5") (pinfunction "Q_5") (pintype "output"))
    )
  )
)
